# Ethernet.net
KiCad netlist of a schematic drawn in Altium Designer
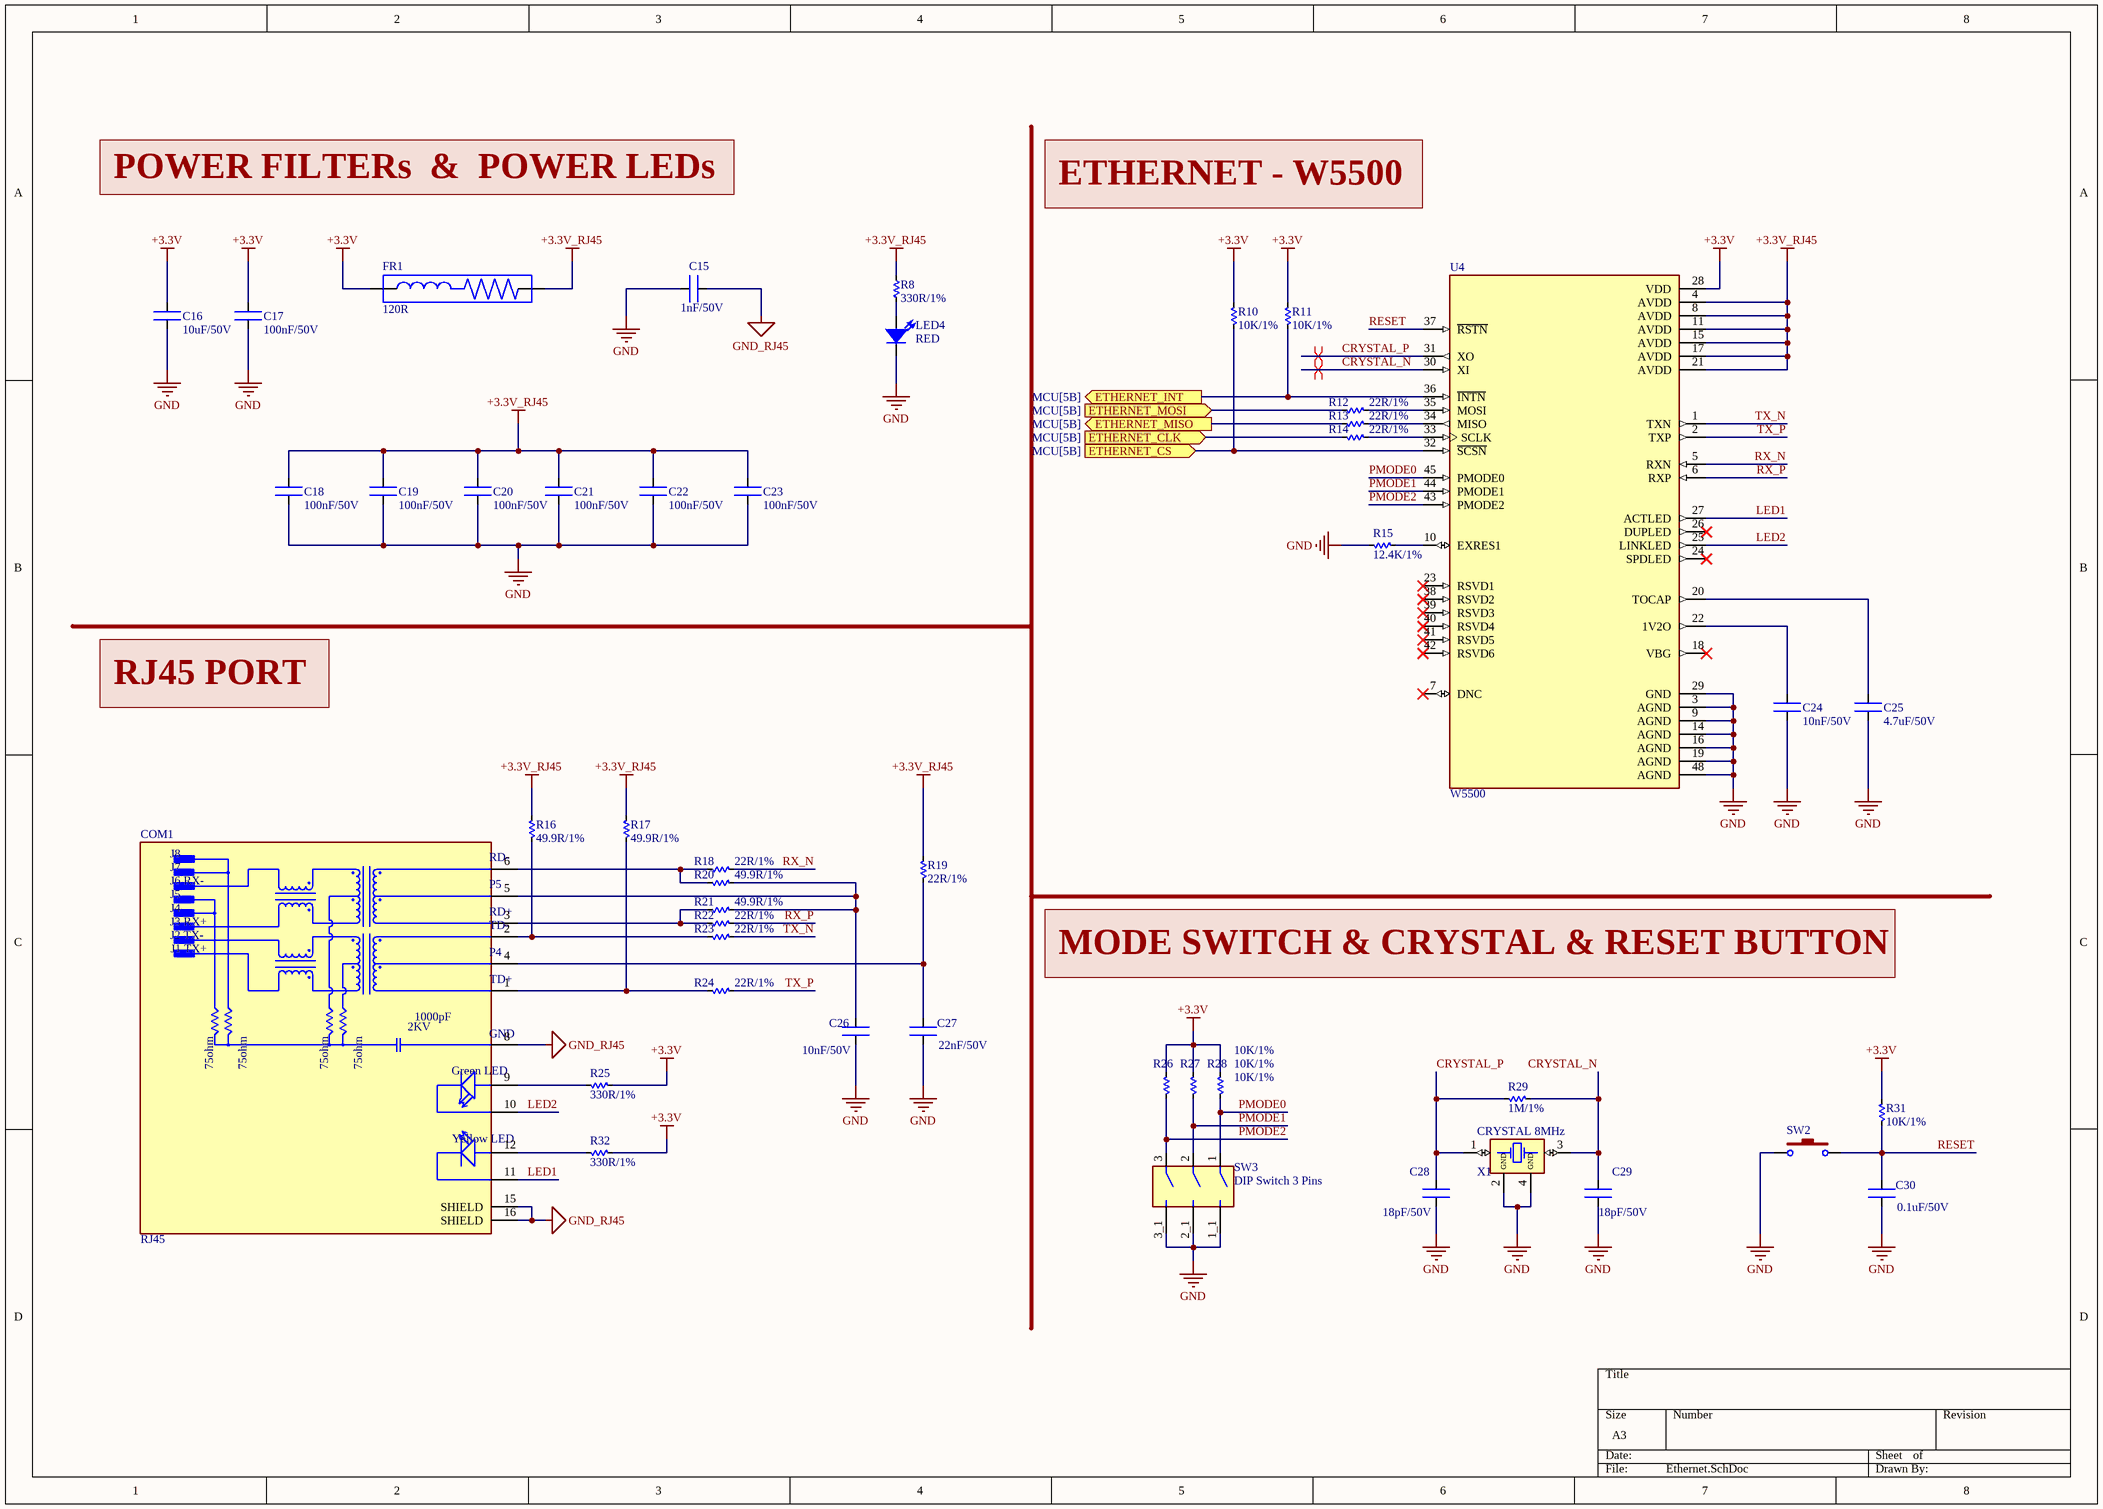
[diagram p0: Ethernet.SchDoc]

(export (version "E")
  (design (tool "Eeschema 10.0.6"))
  (components
    (comp (ref "C15")
      (value "1nF/50V")
      (footprint "CAP - 0603")
      (description "CAPACITOR SMD - KEMET")
      (libsource (lib "NewLibrary") (part "CAPACITOR"))
    )
    (comp (ref "C16")
      (value "10uF/50V")
      (footprint "CAP - 0603")
      (description "CAPACITOR SMD - KEMET")
      (libsource (lib "NewLibrary") (part "CAPACITOR"))
    )
    (comp (ref "C17")
      (value "100nF/50V")
      (footprint "CAP - 0603")
      (description "CAPACITOR SMD - KEMET")
      (libsource (lib "NewLibrary") (part "CAPACITOR"))
    )
    (comp (ref "C18")
      (value "100nF/50V")
      (footprint "CAP - 0603")
      (description "CAPACITOR SMD - KEMET")
      (libsource (lib "NewLibrary") (part "CAPACITOR"))
    )
    (comp (ref "C19")
      (value "100nF/50V")
      (footprint "CAP - 0603")
      (description "CAPACITOR SMD - KEMET")
      (libsource (lib "NewLibrary") (part "CAPACITOR"))
    )
    (comp (ref "C20")
      (value "100nF/50V")
      (footprint "CAP - 0603")
      (description "CAPACITOR SMD - KEMET")
      (libsource (lib "NewLibrary") (part "CAPACITOR"))
    )
    (comp (ref "C21")
      (value "100nF/50V")
      (footprint "CAP - 0603")
      (description "CAPACITOR SMD - KEMET")
      (libsource (lib "NewLibrary") (part "CAPACITOR"))
    )
    (comp (ref "C22")
      (value "100nF/50V")
      (footprint "CAP - 0603")
      (description "CAPACITOR SMD - KEMET")
      (libsource (lib "NewLibrary") (part "CAPACITOR"))
    )
    (comp (ref "C23")
      (value "100nF/50V")
      (footprint "CAP - 0603")
      (description "CAPACITOR SMD - KEMET")
      (libsource (lib "NewLibrary") (part "CAPACITOR"))
    )
    (comp (ref "C24")
      (value "10nF/50V")
      (footprint "CAP - 0603")
      (description "CAPACITOR SMD - KEMET")
      (libsource (lib "NewLibrary") (part "CAPACITOR"))
    )
    (comp (ref "C25")
      (value "4.7uF/50V")
      (footprint "CAP - 0603")
      (description "CAPACITOR SMD - KEMET")
      (libsource (lib "NewLibrary") (part "CAPACITOR"))
    )
    (comp (ref "C26")
      (value "10nF/50V")
      (footprint "CAP - 0603")
      (description "CAPACITOR SMD - KEMET")
      (libsource (lib "NewLibrary") (part "CAPACITOR"))
    )
    (comp (ref "C27")
      (value "22nF/50V")
      (footprint "CAP - 0603")
      (description "CAPACITOR SMD - KEMET")
      (libsource (lib "NewLibrary") (part "CAPACITOR"))
    )
    (comp (ref "C28")
      (value "18pF/50V")
      (footprint "CAP - 0603")
      (description "CAPACITOR SMD - KEMET")
      (libsource (lib "NewLibrary") (part "CAPACITOR"))
    )
    (comp (ref "C29")
      (value "18pF/50V")
      (footprint "CAP - 0603")
      (description "CAPACITOR SMD - KEMET")
      (libsource (lib "NewLibrary") (part "CAPACITOR"))
    )
    (comp (ref "C30")
      (value "0.1uF/50V")
      (footprint "CAP - 0603")
      (description "CAPACITOR SMD - KEMET")
      (libsource (lib "NewLibrary") (part "CAPACITOR"))
    )
    (comp (ref "COM1")
      (value "RJ45")
      (footprint "RJ45")
      (description "HR911105A")
      (libsource (lib "NewLibrary") (part "RJ45"))
    )
    (comp (ref "FR1")
      (value "120R")
      (footprint "FR-0805")
      (description "SMD")
      (libsource (lib "NewLibrary") (part "Ferrite Beads"))
    )
    (comp (ref "LED4")
      (value "RED")
      (footprint "RED_LED_0603")
      (description "LED SMD")
      (libsource (lib "NewLibrary") (part "LED_SMD"))
    )
    (comp (ref "R8")
      (value "330R/1%")
      (footprint "RES - 0603")
      (description "Resistor SMD - YAGEO")
      (libsource (lib "NewLibrary") (part "RESISTOR"))
    )
    (comp (ref "R10")
      (value "10K/1%")
      (footprint "RES - 0603")
      (description "Resistor SMD - YAGEO")
      (libsource (lib "NewLibrary") (part "RESISTOR"))
    )
    (comp (ref "R11")
      (value "10K/1%")
      (footprint "RES - 0603")
      (description "Resistor SMD - YAGEO")
      (libsource (lib "NewLibrary") (part "RESISTOR"))
    )
    (comp (ref "R12")
      (value "22R/1%")
      (footprint "RES - 0603")
      (description "Resistor SMD - YAGEO")
      (libsource (lib "NewLibrary") (part "RESISTOR"))
    )
    (comp (ref "R13")
      (value "22R/1%")
      (footprint "RES - 0603")
      (description "Resistor SMD - YAGEO")
      (libsource (lib "NewLibrary") (part "RESISTOR"))
    )
    (comp (ref "R14")
      (value "22R/1%")
      (footprint "RES - 0603")
      (description "Resistor SMD - YAGEO")
      (libsource (lib "NewLibrary") (part "RESISTOR"))
    )
    (comp (ref "R15")
      (value "12.4K/1%")
      (footprint "RES - 0603")
      (description "Resistor SMD - YAGEO")
      (libsource (lib "NewLibrary") (part "RESISTOR"))
    )
    (comp (ref "R16")
      (value "49.9R/1%")
      (footprint "RES - 0603")
      (description "Resistor SMD - YAGEO")
      (libsource (lib "NewLibrary") (part "RESISTOR"))
    )
    (comp (ref "R17")
      (value "49.9R/1%")
      (footprint "RES - 0603")
      (description "Resistor SMD - YAGEO")
      (libsource (lib "NewLibrary") (part "RESISTOR"))
    )
    (comp (ref "R18")
      (value "22R/1%")
      (footprint "RES - 0603")
      (description "Resistor SMD - YAGEO")
      (libsource (lib "NewLibrary") (part "RESISTOR"))
    )
    (comp (ref "R19")
      (value "22R/1%")
      (footprint "RES - 0603")
      (description "Resistor SMD - YAGEO")
      (libsource (lib "NewLibrary") (part "RESISTOR"))
    )
    (comp (ref "R20")
      (value "49.9R/1%")
      (footprint "RES - 0603")
      (description "Resistor SMD - YAGEO")
      (libsource (lib "NewLibrary") (part "RESISTOR"))
    )
    (comp (ref "R21")
      (value "49.9R/1%")
      (footprint "RES - 0603")
      (description "Resistor SMD - YAGEO")
      (libsource (lib "NewLibrary") (part "RESISTOR"))
    )
    (comp (ref "R22")
      (value "22R/1%")
      (footprint "RES - 0603")
      (description "Resistor SMD - YAGEO")
      (libsource (lib "NewLibrary") (part "RESISTOR"))
    )
    (comp (ref "R23")
      (value "22R/1%")
      (footprint "RES - 0603")
      (description "Resistor SMD - YAGEO")
      (libsource (lib "NewLibrary") (part "RESISTOR"))
    )
    (comp (ref "R24")
      (value "22R/1%")
      (footprint "RES - 0603")
      (description "Resistor SMD - YAGEO")
      (libsource (lib "NewLibrary") (part "RESISTOR"))
    )
    (comp (ref "R25")
      (value "330R/1%")
      (footprint "RES - 0603")
      (description "Resistor SMD - YAGEO")
      (libsource (lib "NewLibrary") (part "RESISTOR"))
    )
    (comp (ref "R26")
      (value "10K/1%")
      (footprint "RES - 0603")
      (description "Resistor SMD - YAGEO")
      (libsource (lib "NewLibrary") (part "RESISTOR"))
    )
    (comp (ref "R27")
      (value "10K/1%")
      (footprint "RES - 0603")
      (description "Resistor SMD - YAGEO")
      (libsource (lib "NewLibrary") (part "RESISTOR"))
    )
    (comp (ref "R28")
      (value "10K/1%")
      (footprint "RES - 0603")
      (description "Resistor SMD - YAGEO")
      (libsource (lib "NewLibrary") (part "RESISTOR"))
    )
    (comp (ref "R29")
      (value "1M/1%")
      (footprint "RES - 0603")
      (description "Resistor SMD - YAGEO")
      (libsource (lib "NewLibrary") (part "RESISTOR"))
    )
    (comp (ref "R31")
      (value "10K/1%")
      (footprint "RES - 0603")
      (description "Resistor SMD - YAGEO")
      (libsource (lib "NewLibrary") (part "RESISTOR"))
    )
    (comp (ref "R32")
      (value "330R/1%")
      (footprint "RES - 0603")
      (description "Resistor SMD - YAGEO")
      (libsource (lib "NewLibrary") (part "RESISTOR"))
    )
    (comp (ref "SW2")
      (value "Button 2 Pins")
      (footprint "SMD SWITCH 2 PINS")
      (description "SMD Button")
      (libsource (lib "NewLibrary") (part "Button 2 Pins"))
    )
    (comp (ref "SW3")
      (value "DIP Switch 3 Pins")
      (footprint "SMD - SW - 3Pins")
      (description "Switch DIP ON OFF SPST 3 Flush Slide 0.1A 20VDC Gull Wing 2000Cycles 2.54mm SMD T/R")
      (libsource (lib "NewLibrary") (part "DIP Switch 3 Pins"))
    )
    (comp (ref "U4")
      (value "W5500")
      (footprint "LQFP-48")
      (description "Hardwired TCP/IP embedded Ethernet controller")
      (libsource (lib "NewLibrary") (part "W5500"))
    )
    (comp (ref "X1")
      (value "CRYSTAL 8MHz")
      (footprint "crystal - 3.2 x 2.5 mm")
      (description "SMD CRYSTAL")
      (libsource (lib "NewLibrary") (part "CRYSTAL 8MHz"))
    )
  )
  (nets
    (net (code "1") (name "+3.3V") (class "Default")
      (node (ref "C16") (pin "2") (pinfunction "2_2") (pintype "passive"))
      (node (ref "C17") (pin "2") (pinfunction "2_2") (pintype "passive"))
      (node (ref "FR1") (pin "1") (pinfunction "1_1") (pintype "passive"))
      (node (ref "R10") (pin "2") (pinfunction "2_2") (pintype "passive"))
      (node (ref "R11") (pin "2") (pinfunction "2_2") (pintype "passive"))
      (node (ref "R25") (pin "1") (pinfunction "1_1") (pintype "passive"))
      (node (ref "R26") (pin "2") (pinfunction "2_2") (pintype "passive"))
      (node (ref "R27") (pin "2") (pinfunction "2_2") (pintype "passive"))
      (node (ref "R28") (pin "2") (pinfunction "2_2") (pintype "passive"))
      (node (ref "R31") (pin "1") (pinfunction "1_1") (pintype "passive"))
      (node (ref "R32") (pin "1") (pinfunction "1_1") (pintype "passive"))
      (node (ref "U4") (pin "28") (pinfunction "VDD_28") (pintype "power_in"))
    )
    (net (code "2") (name "+3.3V_RJ45") (class "Default")
      (node (ref "C18") (pin "2") (pinfunction "2_2") (pintype "passive"))
      (node (ref "C19") (pin "2") (pinfunction "2_2") (pintype "passive"))
      (node (ref "C20") (pin "2") (pinfunction "2_2") (pintype "passive"))
      (node (ref "C21") (pin "2") (pinfunction "2_2") (pintype "passive"))
      (node (ref "C22") (pin "2") (pinfunction "2_2") (pintype "passive"))
      (node (ref "C23") (pin "2") (pinfunction "2_2") (pintype "passive"))
      (node (ref "FR1") (pin "2") (pinfunction "2_2") (pintype "passive"))
      (node (ref "R16") (pin "2") (pinfunction "2_2") (pintype "passive"))
      (node (ref "R17") (pin "2") (pinfunction "2_2") (pintype "passive"))
      (node (ref "R19") (pin "1") (pinfunction "1_1") (pintype "passive"))
      (node (ref "R8") (pin "1") (pinfunction "1_1") (pintype "passive"))
      (node (ref "U4") (pin "11") (pinfunction "AVDD_11") (pintype "power_in"))
      (node (ref "U4") (pin "15") (pinfunction "AVDD_15") (pintype "power_in"))
      (node (ref "U4") (pin "17") (pinfunction "AVDD_17") (pintype "power_in"))
      (node (ref "U4") (pin "21") (pinfunction "AVDD_21") (pintype "power_in"))
      (node (ref "U4") (pin "4") (pinfunction "AVDD_4") (pintype "power_in"))
      (node (ref "U4") (pin "8") (pinfunction "AVDD_8") (pintype "power_in"))
    )
    (net (code "3") (name "/CRYSTAL_N") (class "Default")
      (node (ref "C29") (pin "2") (pinfunction "2_2") (pintype "passive"))
      (node (ref "R29") (pin "1") (pinfunction "1_1") (pintype "passive"))
      (node (ref "U4") (pin "30") (pinfunction "XI_30") (pintype "input"))
      (node (ref "X1") (pin "3") (pinfunction "OUT/IN_3") (pintype "bidirectional"))
    )
    (net (code "4") (name "/CRYSTAL_P") (class "Default")
      (node (ref "C28") (pin "2") (pinfunction "2_2") (pintype "passive"))
      (node (ref "R29") (pin "2") (pinfunction "2_2") (pintype "passive"))
      (node (ref "U4") (pin "31") (pinfunction "XO_31") (pintype "output"))
      (node (ref "X1") (pin "1") (pinfunction "IN/OUT_1") (pintype "bidirectional"))
    )
    (net (code "5") (name "/ETHERNET_CLK") (class "Default")
      (node (ref "R14") (pin "2") (pinfunction "2_2") (pintype "passive"))
    )
    (net (code "6") (name "/ETHERNET_CS") (class "Default")
      (node (ref "R10") (pin "1") (pinfunction "1_1") (pintype "passive"))
      (node (ref "U4") (pin "32") (pinfunction "~{SCSN}_32") (pintype "input"))
    )
    (net (code "7") (name "/ETHERNET_INT") (class "Default")
      (node (ref "R11") (pin "1") (pinfunction "1_1") (pintype "passive"))
      (node (ref "U4") (pin "36") (pinfunction "~{INTN}_36") (pintype "input"))
    )
    (net (code "8") (name "/ETHERNET_MISO") (class "Default")
      (node (ref "R13") (pin "2") (pinfunction "2_2") (pintype "passive"))
    )
    (net (code "9") (name "/ETHERNET_MOSI") (class "Default")
      (node (ref "R12") (pin "2") (pinfunction "2_2") (pintype "passive"))
    )
    (net (code "10") (name "/LED1") (class "Default")
      (node (ref "COM1") (pin "11") (pinfunction "YC_11") (pintype "passive"))
      (node (ref "U4") (pin "27") (pinfunction "ACTLED_27") (pintype "output"))
    )
    (net (code "11") (name "/LED2") (class "Default")
      (node (ref "COM1") (pin "10") (pinfunction "GC_10") (pintype "passive"))
      (node (ref "U4") (pin "25") (pinfunction "LINKLED_25") (pintype "output"))
    )
    (net (code "12") (name "/PMODE0") (class "Default")
      (node (ref "R28") (pin "1") (pinfunction "1_1") (pintype "passive"))
      (node (ref "SW3") (pin "1") (pinfunction "1_1") (pintype "passive"))
      (node (ref "U4") (pin "45") (pinfunction "PMODE0_45") (pintype "input"))
    )
    (net (code "13") (name "/PMODE1") (class "Default")
      (node (ref "R27") (pin "1") (pinfunction "1_1") (pintype "passive"))
      (node (ref "SW3") (pin "2") (pinfunction "2_2") (pintype "passive"))
      (node (ref "U4") (pin "44") (pinfunction "PMODE1_44") (pintype "input"))
    )
    (net (code "14") (name "/PMODE2") (class "Default")
      (node (ref "R26") (pin "1") (pinfunction "1_1") (pintype "passive"))
      (node (ref "SW3") (pin "3") (pinfunction "3_3") (pintype "passive"))
      (node (ref "U4") (pin "43") (pinfunction "PMODE2_43") (pintype "input"))
    )
    (net (code "15") (name "/RESET") (class "Default")
      (node (ref "C30") (pin "2") (pinfunction "2_2") (pintype "passive"))
      (node (ref "R31") (pin "2") (pinfunction "2_2") (pintype "passive"))
      (node (ref "SW2") (pin "2") (pinfunction "2_2") (pintype "passive"))
      (node (ref "U4") (pin "37") (pinfunction "~{RSTN}_37") (pintype "input"))
    )
    (net (code "16") (name "/RX_N") (class "Default")
      (node (ref "R18") (pin "1") (pinfunction "1_1") (pintype "passive"))
      (node (ref "U4") (pin "5") (pinfunction "RXN_5") (pintype "input"))
    )
    (net (code "17") (name "/RX_P") (class "Default")
      (node (ref "R22") (pin "1") (pinfunction "1_1") (pintype "passive"))
      (node (ref "U4") (pin "6") (pinfunction "RXP_6") (pintype "input"))
    )
    (net (code "18") (name "/TX_N") (class "Default")
      (node (ref "R23") (pin "1") (pinfunction "1_1") (pintype "passive"))
      (node (ref "U4") (pin "1") (pinfunction "TXN_1") (pintype "output"))
    )
    (net (code "19") (name "/TX_P") (class "Default")
      (node (ref "R24") (pin "1") (pinfunction "1_1") (pintype "passive"))
      (node (ref "U4") (pin "2") (pinfunction "TXP_2") (pintype "output"))
    )
    (net (code "20") (name "GND") (class "Default")
      (node (ref "C15") (pin "1") (pinfunction "1_1") (pintype "passive"))
      (node (ref "C16") (pin "1") (pinfunction "1_1") (pintype "passive"))
      (node (ref "C17") (pin "1") (pinfunction "1_1") (pintype "passive"))
      (node (ref "C18") (pin "1") (pinfunction "1_1") (pintype "passive"))
      (node (ref "C19") (pin "1") (pinfunction "1_1") (pintype "passive"))
      (node (ref "C20") (pin "1") (pinfunction "1_1") (pintype "passive"))
      (node (ref "C21") (pin "1") (pinfunction "1_1") (pintype "passive"))
      (node (ref "C22") (pin "1") (pinfunction "1_1") (pintype "passive"))
      (node (ref "C23") (pin "1") (pinfunction "1_1") (pintype "passive"))
      (node (ref "C24") (pin "1") (pinfunction "1_1") (pintype "passive"))
      (node (ref "C25") (pin "1") (pinfunction "1_1") (pintype "passive"))
      (node (ref "C26") (pin "1") (pinfunction "1_1") (pintype "passive"))
      (node (ref "C27") (pin "1") (pinfunction "1_1") (pintype "passive"))
      (node (ref "C28") (pin "1") (pinfunction "1_1") (pintype "passive"))
      (node (ref "C29") (pin "1") (pinfunction "1_1") (pintype "passive"))
      (node (ref "C30") (pin "1") (pinfunction "1_1") (pintype "passive"))
      (node (ref "LED4") (pin "2") (pinfunction "2_2") (pintype "passive"))
      (node (ref "R15") (pin "1") (pinfunction "1_1") (pintype "passive"))
      (node (ref "SW2") (pin "1") (pinfunction "1_1") (pintype "passive"))
      (node (ref "SW3") (pin "1_1") (pinfunction "1_1_1_1") (pintype "passive"))
      (node (ref "SW3") (pin "2_1") (pinfunction "2_1_2_1") (pintype "passive"))
      (node (ref "SW3") (pin "3_1") (pinfunction "3_1_3_1") (pintype "passive"))
      (node (ref "U4") (pin "14") (pinfunction "AGND_14") (pintype "power_in"))
      (node (ref "U4") (pin "16") (pinfunction "AGND_16") (pintype "power_in"))
      (node (ref "U4") (pin "19") (pinfunction "AGND_19") (pintype "power_in"))
      (node (ref "U4") (pin "29") (pinfunction "GND_29") (pintype "passive"))
      (node (ref "U4") (pin "3") (pinfunction "AGND_3") (pintype "power_in"))
      (node (ref "U4") (pin "48") (pinfunction "AGND_48") (pintype "power_in"))
      (node (ref "U4") (pin "9") (pinfunction "AGND_9") (pintype "power_in"))
      (node (ref "X1") (pin "2") (pinfunction "GND_2") (pintype "power_in"))
      (node (ref "X1") (pin "4") (pinfunction "GND_4") (pintype "power_in"))
    )
    (net (code "21") (name "GND_RJ45") (class "Default")
      (node (ref "C15") (pin "2") (pinfunction "2_2") (pintype "passive"))
      (node (ref "COM1") (pin "15") (pinfunction "SHIELD_15") (pintype "passive"))
      (node (ref "COM1") (pin "16") (pinfunction "SHIELD_16") (pintype "passive"))
      (node (ref "COM1") (pin "8") (pinfunction "GND_8") (pintype "power_in"))
    )
    (net (code "22") (name "Net-(COM1-GA)") (class "Default")
      (node (ref "COM1") (pin "9") (pinfunction "GA_9") (pintype "passive"))
      (node (ref "R25") (pin "2") (pinfunction "2_2") (pintype "passive"))
    )
    (net (code "23") (name "Net-(COM1-P4)") (class "Default")
      (node (ref "C27") (pin "2") (pinfunction "2_2") (pintype "passive"))
      (node (ref "COM1") (pin "4") (pinfunction "P4_4") (pintype "passive"))
      (node (ref "R19") (pin "2") (pinfunction "2_2") (pintype "passive"))
    )
    (net (code "24") (name "Net-(COM1-P5)") (class "Default")
      (node (ref "C26") (pin "2") (pinfunction "2_2") (pintype "passive"))
      (node (ref "COM1") (pin "5") (pinfunction "P5_5") (pintype "passive"))
      (node (ref "R20") (pin "1") (pinfunction "1_1") (pintype "passive"))
      (node (ref "R21") (pin "1") (pinfunction "1_1") (pintype "passive"))
    )
    (net (code "25") (name "Net-(COM1-RD+)") (class "Default")
      (node (ref "COM1") (pin "3") (pinfunction "RD+_3") (pintype "passive"))
      (node (ref "R21") (pin "2") (pinfunction "2_2") (pintype "passive"))
      (node (ref "R22") (pin "2") (pinfunction "2_2") (pintype "passive"))
    )
    (net (code "26") (name "Net-(COM1-RD-)") (class "Default")
      (node (ref "COM1") (pin "6") (pinfunction "RD-_6") (pintype "passive"))
      (node (ref "R18") (pin "2") (pinfunction "2_2") (pintype "passive"))
      (node (ref "R20") (pin "2") (pinfunction "2_2") (pintype "passive"))
    )
    (net (code "27") (name "Net-(COM1-TD+)") (class "Default")
      (node (ref "COM1") (pin "1") (pinfunction "TD+_1") (pintype "passive"))
      (node (ref "R17") (pin "1") (pinfunction "1_1") (pintype "passive"))
      (node (ref "R24") (pin "2") (pinfunction "2_2") (pintype "passive"))
    )
    (net (code "28") (name "Net-(COM1-TD-)") (class "Default")
      (node (ref "COM1") (pin "2") (pinfunction "TD-_2") (pintype "passive"))
      (node (ref "R16") (pin "1") (pinfunction "1_1") (pintype "passive"))
      (node (ref "R23") (pin "2") (pinfunction "2_2") (pintype "passive"))
    )
    (net (code "29") (name "Net-(COM1-YA)") (class "Default")
      (node (ref "COM1") (pin "12") (pinfunction "YA_12") (pintype "passive"))
      (node (ref "R32") (pin "2") (pinfunction "2_2") (pintype "passive"))
    )
    (net (code "30") (name "Net-(LED4-Pad1)") (class "Default")
      (node (ref "LED4") (pin "1") (pinfunction "1_1") (pintype "passive"))
      (node (ref "R8") (pin "2") (pinfunction "2_2") (pintype "passive"))
    )
    (net (code "31") (name "Net-(U4-1V2O)") (class "Default")
      (node (ref "C24") (pin "2") (pinfunction "2_2") (pintype "passive"))
      (node (ref "U4") (pin "22") (pinfunction "1V2O_22") (pintype "output"))
    )
    (net (code "32") (name "Net-(U4-EXRES1)") (class "Default")
      (node (ref "R15") (pin "2") (pinfunction "2_2") (pintype "passive"))
      (node (ref "U4") (pin "10") (pinfunction "EXRES1_10") (pintype "bidirectional"))
    )
    (net (code "33") (name "Net-(U4-MISO)") (class "Default")
      (node (ref "R13") (pin "1") (pinfunction "1_1") (pintype "passive"))
      (node (ref "U4") (pin "34") (pinfunction "MISO_34") (pintype "output"))
    )
    (net (code "34") (name "Net-(U4-MOSI)") (class "Default")
      (node (ref "R12") (pin "1") (pinfunction "1_1") (pintype "passive"))
      (node (ref "U4") (pin "35") (pinfunction "MOSI_35") (pintype "input"))
    )
    (net (code "35") (name "Net-(U4-SCLK)") (class "Default")
      (node (ref "R14") (pin "1") (pinfunction "1_1") (pintype "passive"))
      (node (ref "U4") (pin "33") (pinfunction "SCLK_33") (pintype "input"))
    )
    (net (code "36") (name "Net-(U4-TOCAP)") (class "Default")
      (node (ref "C25") (pin "2") (pinfunction "2_2") (pintype "passive"))
      (node (ref "U4") (pin "20") (pinfunction "TOCAP_20") (pintype "output"))
    )
    (net (code "37") (name "unconnected-(U4-DNC-Pad7)") (class "Default")
      (node (ref "U4") (pin "7") (pinfunction "DNC_7") (pintype "bidirectional+no_connect"))
    )
    (net (code "38") (name "unconnected-(U4-DUPLED-Pad26)") (class "Default")
      (node (ref "U4") (pin "26") (pinfunction "DUPLED_26") (pintype "output+no_connect"))
    )
    (net (code "39") (name "unconnected-(U4-RSVD1-Pad23)") (class "Default")
      (node (ref "U4") (pin "23") (pinfunction "RSVD1_23") (pintype "input+no_connect"))
    )
    (net (code "40") (name "unconnected-(U4-RSVD2-Pad38)") (class "Default")
      (node (ref "U4") (pin "38") (pinfunction "RSVD2_38") (pintype "input+no_connect"))
    )
    (net (code "41") (name "unconnected-(U4-RSVD3-Pad39)") (class "Default")
      (node (ref "U4") (pin "39") (pinfunction "RSVD3_39") (pintype "input+no_connect"))
    )
    (net (code "42") (name "unconnected-(U4-RSVD4-Pad40)") (class "Default")
      (node (ref "U4") (pin "40") (pinfunction "RSVD4_40") (pintype "input+no_connect"))
    )
    (net (code "43") (name "unconnected-(U4-RSVD5-Pad41)") (class "Default")
      (node (ref "U4") (pin "41") (pinfunction "RSVD5_41") (pintype "input+no_connect"))
    )
    (net (code "44") (name "unconnected-(U4-RSVD6-Pad42)") (class "Default")
      (node (ref "U4") (pin "42") (pinfunction "RSVD6_42") (pintype "input+no_connect"))
    )
    (net (code "45") (name "unconnected-(U4-SPDLED-Pad24)") (class "Default")
      (node (ref "U4") (pin "24") (pinfunction "SPDLED_24") (pintype "output+no_connect"))
    )
    (net (code "46") (name "unconnected-(U4-VBG-Pad18)") (class "Default")
      (node (ref "U4") (pin "18") (pinfunction "VBG_18") (pintype "output+no_connect"))
    )
  )
)
